# TOP.net
KiCad netlist of a schematic drawn in Altium Designer
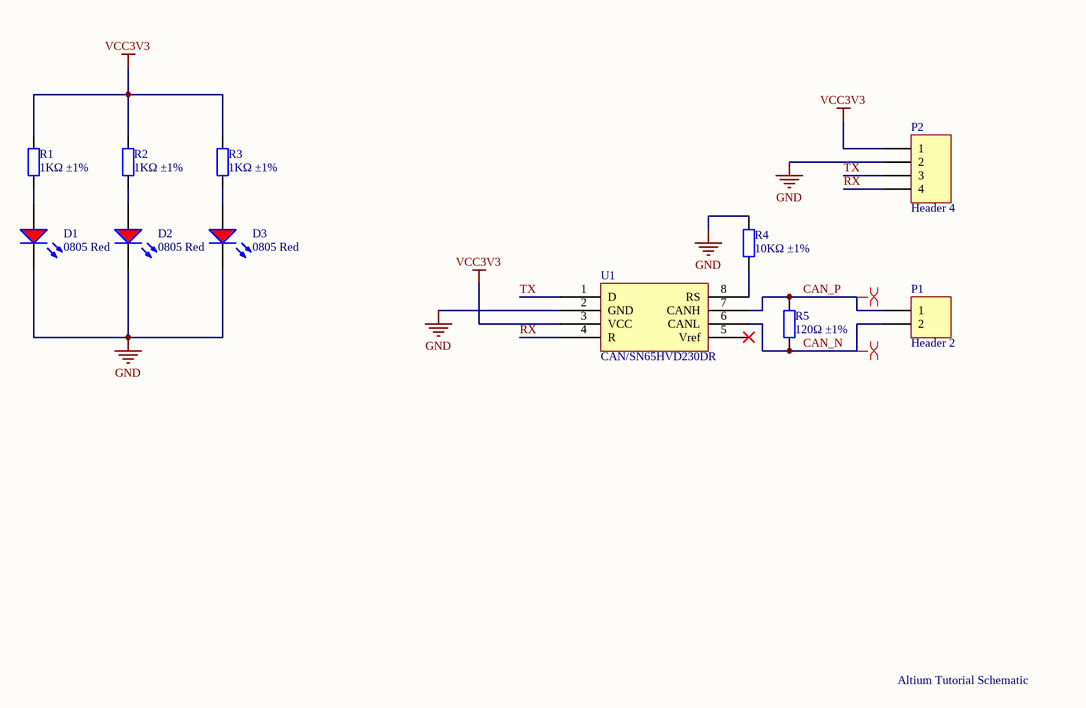
[diagram p0: TOP.SchDoc]

(export (version "E")
  (design (tool "Eeschema 10.0.6"))
  (components
    (comp (ref "D1")
      (value "0805 Red")
      (footprint "0805_LED_S1")
      (description "LED")
      (fields
        (field (name "PARTNUMBER") "FC-2012HRK-620D")
        (field (name "MANUFACTURER") "Foshan NationStar Optoelectronics")
      )
      (libsource (lib "LED") (part "0805 LED Red"))
    )
    (comp (ref "D2")
      (value "0805 Red")
      (footprint "0805_LED_S1")
      (description "LED")
      (fields
        (field (name "PARTNUMBER") "FC-2012HRK-620D")
        (field (name "MANUFACTURER") "Foshan NationStar Optoelectronics")
      )
      (libsource (lib "LED") (part "0805 LED Red"))
    )
    (comp (ref "D3")
      (value "0805 Red")
      (footprint "0805_LED_S1")
      (description "LED")
      (fields
        (field (name "PARTNUMBER") "FC-2012HRK-620D")
        (field (name "MANUFACTURER") "Foshan NationStar Optoelectronics")
      )
      (libsource (lib "LED") (part "0805 LED Red"))
    )
    (comp (ref "P1")
      (value "Header 2")
      (footprint "HDR1X2")
      (description "Header, 2-Pin")
      (fields (field (name "PUBLISHER") "Altium Limited"))
      (libsource (lib "Miscellaneous Connectors") (part "Header 2"))
    )
    (comp (ref "P2")
      (value "Header 4")
      (footprint "HDR1X4")
      (description "Header, 4-Pin")
      (fields (field (name "PUBLISHER") "Altium Limited"))
      (libsource (lib "Miscellaneous Connectors") (part "Header 4"))
    )
    (comp (ref "R1")
      (value "1KΩ ±1%")
      (footprint "0805_R")
      (description "Chip resistor")
      (fields (field (name "MANUFACTURER") "Uniroyal Elec") (field (name "PARTNUMBER") "0805W8F1001T5E"))
      (libsource (lib "RES") (part "0805 1K (1001) 1%"))
    )
    (comp (ref "R2")
      (value "1KΩ ±1%")
      (footprint "0805_R")
      (description "Chip resistor")
      (fields (field (name "MANUFACTURER") "Uniroyal Elec") (field (name "PARTNUMBER") "0805W8F1001T5E"))
      (libsource (lib "") (part "0805 1K (1001) 1%_1"))
    )
    (comp (ref "R3")
      (value "1KΩ ±1%")
      (footprint "0805_R")
      (description "Chip resistor")
      (fields (field (name "MANUFACTURER") "Uniroyal Elec") (field (name "PARTNUMBER") "0805W8F1001T5E"))
      (libsource (lib "RES") (part "0805 1K (1001) 1%"))
    )
    (comp (ref "R4")
      (value "10KΩ ±1%")
      (footprint "0402_R")
      (description "Chip resistor")
      (fields (field (name "MANUFACTURER") "Uniroyal Elec") (field (name "PARTNUMBER") "0402WGF1002TCE"))
      (libsource (lib "RES") (part "0402 10K (1002) 1%"))
    )
    (comp (ref "R5")
      (value "120Ω ±1%")
      (footprint "0402_R")
      (description "Chip resistor")
      (fields (field (name "MANUFACTURER") "Uniroyal Elec") (field (name "PARTNUMBER") "0402WGF1200TCE"))
      (libsource (lib "RES") (part "0402 120R (1200) 1%"))
    )
    (comp (ref "U1")
      (value "CAN/SN65HVD230DR")
      (footprint "SOIC-8_150mil")
      (description "CAN")
      (libsource (lib "IC") (part "CAN/SN65HVD230DR_[C12084]"))
    )
  )
  (nets
    (net (code "1") (name "/CAN_N") (class "Default")
      (node (ref "P1") (pin "2") (pinfunction "2_2") (pintype "passive"))
      (node (ref "R5") (pin "1") (pinfunction "1_1") (pintype "passive"))
      (node (ref "U1") (pin "6") (pinfunction "CANL_6") (pintype "passive"))
    )
    (net (code "2") (name "/CAN_P") (class "Default")
      (node (ref "P1") (pin "1") (pinfunction "1_1") (pintype "passive"))
      (node (ref "R5") (pin "2") (pinfunction "2_2") (pintype "passive"))
      (node (ref "U1") (pin "7") (pinfunction "CANH_7") (pintype "passive"))
    )
    (net (code "3") (name "/RX") (class "Default")
      (node (ref "P2") (pin "4") (pinfunction "4_4") (pintype "passive"))
      (node (ref "U1") (pin "4") (pinfunction "R_4") (pintype "passive"))
    )
    (net (code "4") (name "/TX") (class "Default")
      (node (ref "P2") (pin "3") (pinfunction "3_3") (pintype "passive"))
      (node (ref "U1") (pin "1") (pinfunction "D_1") (pintype "passive"))
    )
    (net (code "5") (name "GND") (class "Default")
      (node (ref "D1") (pin "K") (pinfunction "K_K") (pintype "passive"))
      (node (ref "D2") (pin "K") (pinfunction "K_K") (pintype "passive"))
      (node (ref "D3") (pin "K") (pinfunction "K_K") (pintype "passive"))
      (node (ref "P2") (pin "2") (pinfunction "2_2") (pintype "passive"))
      (node (ref "R4") (pin "2") (pinfunction "2_2") (pintype "passive"))
      (node (ref "U1") (pin "2") (pinfunction "GND_2") (pintype "passive"))
    )
    (net (code "6") (name "Net-(D1-PadA)") (class "Default")
      (node (ref "D1") (pin "A") (pinfunction "A_A") (pintype "passive"))
      (node (ref "R1") (pin "1") (pinfunction "1_1") (pintype "passive"))
    )
    (net (code "7") (name "Net-(D2-PadA)") (class "Default")
      (node (ref "D2") (pin "A") (pinfunction "A_A") (pintype "passive"))
      (node (ref "R2") (pin "2") (pinfunction "2_2") (pintype "passive"))
    )
    (net (code "8") (name "Net-(D3-PadA)") (class "Default")
      (node (ref "D3") (pin "A") (pinfunction "A_A") (pintype "passive"))
      (node (ref "R3") (pin "1") (pinfunction "1_1") (pintype "passive"))
    )
    (net (code "9") (name "Net-(U1-RS)") (class "Default")
      (node (ref "R4") (pin "1") (pinfunction "1_1") (pintype "passive"))
      (node (ref "U1") (pin "8") (pinfunction "RS_8") (pintype "passive"))
    )
    (net (code "10") (name "VCC3V3") (class "Default")
      (node (ref "P2") (pin "1") (pinfunction "1_1") (pintype "passive"))
      (node (ref "R1") (pin "2") (pinfunction "2_2") (pintype "passive"))
      (node (ref "R2") (pin "1") (pinfunction "1_1") (pintype "passive"))
      (node (ref "R3") (pin "2") (pinfunction "2_2") (pintype "passive"))
      (node (ref "U1") (pin "3") (pinfunction "VCC_3") (pintype "passive"))
    )
    (net (code "11") (name "unconnected-(U1-Vref-Pad5)") (class "Default")
      (node (ref "U1") (pin "5") (pinfunction "Vref_5") (pintype "passive+no_connect"))
    )
  )
)
